# CPU_Board_Connectors.net
KiCad netlist of a schematic drawn in Altium Designer
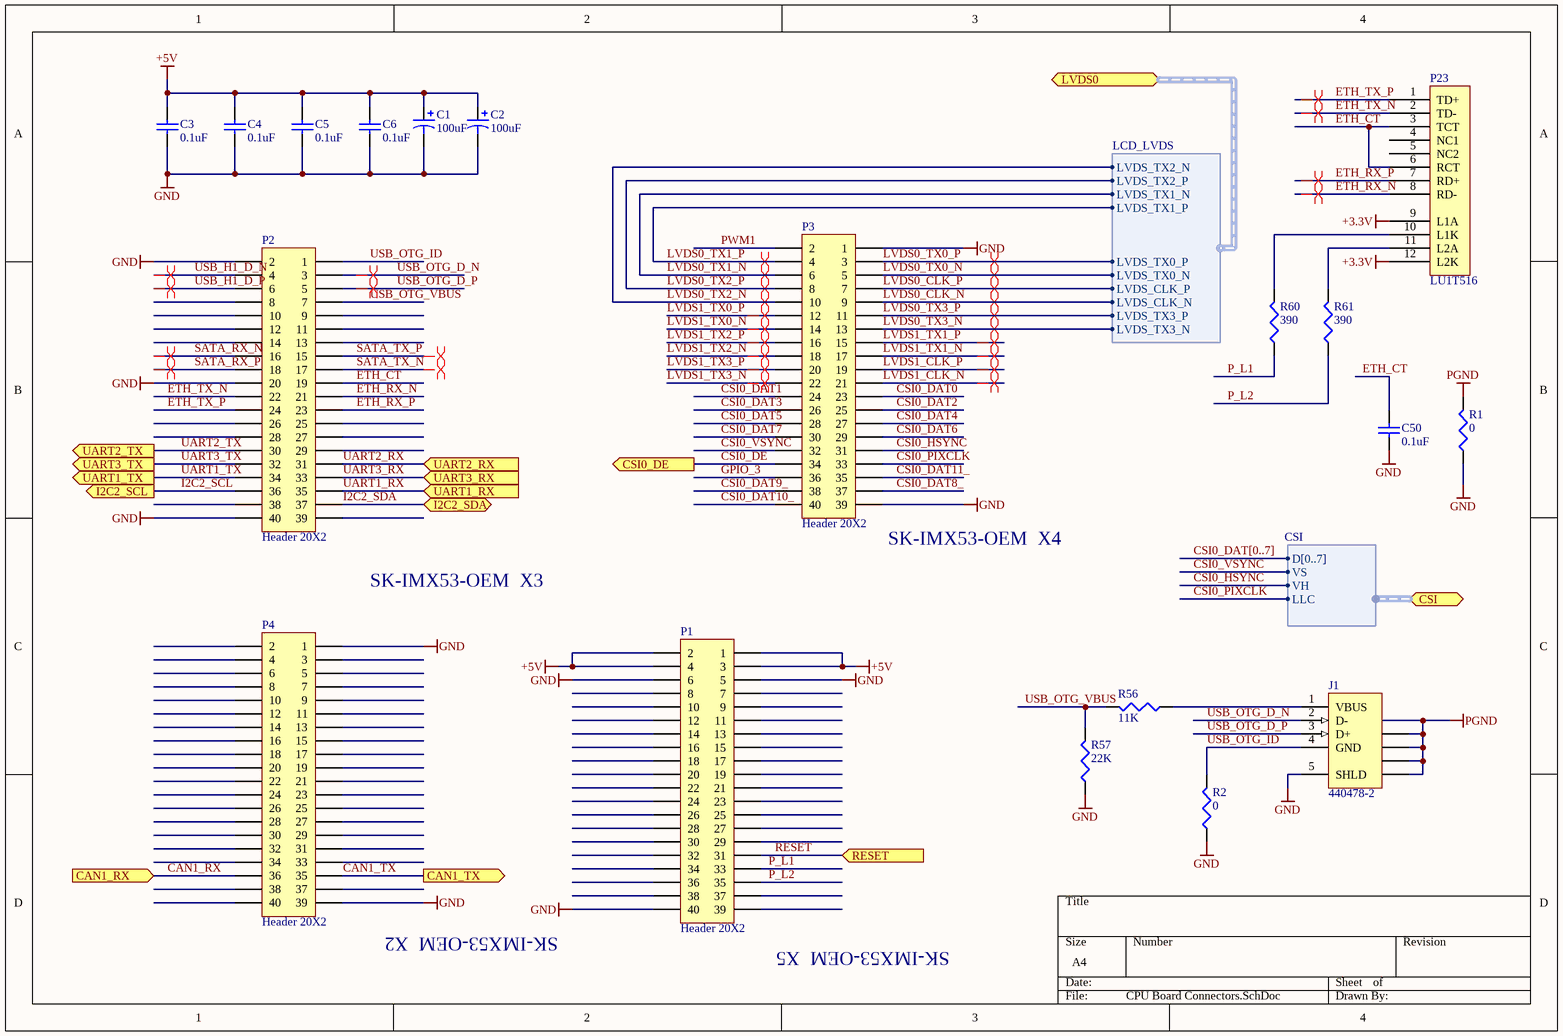
[diagram p0: CPU Board Connectors.SchDoc]

(export (version "E")
  (design (tool "Eeschema 10.0.6"))
  (components
    (comp (ref "C1")
      (value "100uF")
      (footprint "6032")
      (fields (field (name "PUBLISHER") "Altium Limited"))
      (libsource (lib "Vishay Sprague Tantalum Chip Capacitor") (part "893D225X0025C2"))
    )
    (comp (ref "C2")
      (value "100uF")
      (footprint "6032")
      (fields (field (name "PUBLISHER") "Altium Limited"))
      (libsource (lib "Vishay Sprague Tantalum Chip Capacitor") (part "893D225X0025C2"))
    )
    (comp (ref "C3")
      (value "0.1uF")
      (footprint "2012[0805]")
      (description "Ceramic Chip Capacitor - Standard")
      (fields (field (name "PUBLISHER") "Altium Limited"))
      (libsource (lib "ResAndCaps") (part "C0805"))
    )
    (comp (ref "C4")
      (value "0.1uF")
      (footprint "2012[0805]")
      (description "Ceramic Chip Capacitor - Standard")
      (fields (field (name "PUBLISHER") "Altium Limited"))
      (libsource (lib "ResAndCaps") (part "C0805"))
    )
    (comp (ref "C5")
      (value "0.1uF")
      (footprint "2012[0805]")
      (description "Ceramic Chip Capacitor - Standard")
      (fields (field (name "PUBLISHER") "Altium Limited"))
      (libsource (lib "ResAndCaps") (part "C0805"))
    )
    (comp (ref "C6")
      (value "0.1uF")
      (footprint "2012[0805]")
      (description "Ceramic Chip Capacitor - Standard")
      (fields (field (name "PUBLISHER") "Altium Limited"))
      (libsource (lib "ResAndCaps") (part "C0805"))
    )
    (comp (ref "C50")
      (value "0.1uF")
      (footprint "2012[0805]")
      (description "Ceramic Chip Capacitor - Standard")
      (fields (field (name "PUBLISHER") "Altium Limited"))
      (libsource (lib "ResAndCaps") (part "C0805"))
    )
    (comp (ref "J1")
      (value "440478-2")
      (footprint "440478")
      (description "USB 2.0, Right Angle, SMT, A Type, Receptacle, 5 Position, Black")
      (fields (field (name "PUBLISHER") "Altium Limited"))
      (libsource (lib "AMP Serial Bus USB") (part "440478-2"))
    )
    (comp (ref "P1")
      (value "Header 20X2")
      (footprint "HDR2X20_F")
      (description "Header, 20-Pin, Dual row")
      (fields (field (name "PUBLISHER") "Altium Limited"))
      (libsource (lib "Miscellaneous Connectors") (part "Header 20X2"))
    )
    (comp (ref "P2")
      (value "Header 20X2")
      (footprint "HDR2X20_F")
      (description "Header, 20-Pin, Dual row")
      (fields (field (name "PUBLISHER") "Altium Limited"))
      (libsource (lib "Miscellaneous Connectors") (part "Header 20X2"))
    )
    (comp (ref "P3")
      (value "Header 20X2")
      (footprint "HDR2X20_F")
      (description "Header, 20-Pin, Dual row")
      (fields (field (name "PUBLISHER") "Altium Limited"))
      (libsource (lib "Miscellaneous Connectors") (part "Header 20X2"))
    )
    (comp (ref "P4")
      (value "Header 20X2")
      (footprint "HDR2X20_F")
      (description "Header, 20-Pin, Dual row")
      (fields (field (name "PUBLISHER") "Altium Limited"))
      (libsource (lib "Miscellaneous Connectors") (part "Header 20X2"))
    )
    (comp (ref "P23")
      (value "LU1T516")
      (footprint "LU1T516")
      (libsource (lib "ethernet_conns") (part "LU1T516"))
    )
    (comp (ref "R1")
      (value "0")
      (footprint "R2012[0805]")
      (description "R0805")
      (fields (field (name "PUBLISHER") "Altium Limited"))
      (libsource (lib "ResAndCaps") (part "R0805"))
    )
    (comp (ref "R2")
      (value "0")
      (footprint "R2012[0805]")
      (description "R0805")
      (fields (field (name "PUBLISHER") "Altium Limited"))
      (libsource (lib "ResAndCaps") (part "R0805"))
    )
    (comp (ref "R56")
      (value "11K")
      (footprint "R2012[0805]")
      (description "R0805")
      (fields (field (name "PUBLISHER") "Altium Limited"))
      (libsource (lib "ResAndCaps") (part "R0805"))
    )
    (comp (ref "R57")
      (value "22K")
      (footprint "R2012[0805]")
      (description "R0805")
      (fields (field (name "PUBLISHER") "Altium Limited"))
      (libsource (lib "ResAndCaps") (part "R0805"))
    )
    (comp (ref "R60")
      (value "390")
      (footprint "R2012[0805]")
      (description "R0805")
      (fields (field (name "PUBLISHER") "Altium Limited"))
      (libsource (lib "ResAndCaps") (part "R0805"))
    )
    (comp (ref "R61")
      (value "390")
      (footprint "R2012[0805]")
      (description "R0805")
      (fields (field (name "PUBLISHER") "Altium Limited"))
      (libsource (lib "ResAndCaps") (part "R0805"))
    )
  )
  (nets
    (net (code "3") (name "+3.3V") (class "Default")
      (node (ref "P23") (pin "12") (pinfunction "L2K_12") (pintype "passive"))
      (node (ref "P23") (pin "9") (pinfunction "L1A_9") (pintype "passive"))
    )
    (net (code "4") (name "+5V") (class "Default")
      (node (ref "C1") (pin "1") (pinfunction "1_1") (pintype "passive"))
      (node (ref "C2") (pin "1") (pinfunction "1_1") (pintype "passive"))
      (node (ref "C3") (pin "2") (pinfunction "2_2") (pintype "passive"))
      (node (ref "C4") (pin "2") (pinfunction "2_2") (pintype "passive"))
      (node (ref "C5") (pin "2") (pinfunction "2_2") (pintype "passive"))
      (node (ref "C6") (pin "2") (pinfunction "2_2") (pintype "passive"))
      (node (ref "P1") (pin "1") (pinfunction "1_1") (pintype "passive"))
      (node (ref "P1") (pin "2") (pinfunction "2_2") (pintype "passive"))
      (node (ref "P1") (pin "3") (pinfunction "3_3") (pintype "passive"))
      (node (ref "P1") (pin "4") (pinfunction "4_4") (pintype "passive"))
    )
    (net (code "5") (name "/CAN1_RX") (class "Default")
      (node (ref "P4") (pin "36") (pinfunction "36_36") (pintype "passive"))
    )
    (net (code "6") (name "/CAN1_TX") (class "Default")
      (node (ref "P4") (pin "35") (pinfunction "35_35") (pintype "passive"))
    )
    (net (code "7") (name "/CSI0_DAT0") (class "Default")
      (node (ref "P3") (pin "23") (pinfunction "23_23") (pintype "passive"))
    )
    (net (code "8") (name "/CSI0_DAT1") (class "Default")
      (node (ref "P3") (pin "24") (pinfunction "24_24") (pintype "passive"))
    )
    (net (code "9") (name "/CSI0_DAT2") (class "Default")
      (node (ref "P3") (pin "25") (pinfunction "25_25") (pintype "passive"))
    )
    (net (code "10") (name "/CSI0_DAT3") (class "Default")
      (node (ref "P3") (pin "26") (pinfunction "26_26") (pintype "passive"))
    )
    (net (code "11") (name "/CSI0_DAT4") (class "Default")
      (node (ref "P3") (pin "27") (pinfunction "27_27") (pintype "passive"))
    )
    (net (code "12") (name "/CSI0_DAT5") (class "Default")
      (node (ref "P3") (pin "28") (pinfunction "28_28") (pintype "passive"))
    )
    (net (code "13") (name "/CSI0_DAT6") (class "Default")
      (node (ref "P3") (pin "29") (pinfunction "29_29") (pintype "passive"))
    )
    (net (code "14") (name "/CSI0_DAT7") (class "Default")
      (node (ref "P3") (pin "30") (pinfunction "30_30") (pintype "passive"))
    )
    (net (code "15") (name "/CSI0_DAT8_") (class "Default")
      (node (ref "P3") (pin "37") (pinfunction "37_37") (pintype "passive"))
    )
    (net (code "16") (name "/CSI0_DAT9_") (class "Default")
      (node (ref "P3") (pin "38") (pinfunction "38_38") (pintype "passive"))
    )
    (net (code "17") (name "/CSI0_DAT10_") (class "Default")
      (node (ref "P3") (pin "40") (pinfunction "40_40") (pintype "passive"))
    )
    (net (code "18") (name "/CSI0_DAT11_") (class "Default")
      (node (ref "P3") (pin "35") (pinfunction "35_35") (pintype "passive"))
    )
    (net (code "19") (name "/CSI0_DE") (class "Default")
      (node (ref "P3") (pin "34") (pinfunction "34_34") (pintype "passive"))
    )
    (net (code "20") (name "/CSI0_HSYNC") (class "Default")
      (node (ref "P3") (pin "31") (pinfunction "31_31") (pintype "passive"))
    )
    (net (code "21") (name "/CSI0_PIXCLK") (class "Default")
      (node (ref "P3") (pin "33") (pinfunction "33_33") (pintype "passive"))
    )
    (net (code "22") (name "/CSI0_VSYNC") (class "Default")
      (node (ref "P3") (pin "32") (pinfunction "32_32") (pintype "passive"))
    )
    (net (code "24") (name "/ETH_CT") (class "Default")
      (node (ref "C50") (pin "1") (pinfunction "1_1") (pintype "passive"))
      (node (ref "P2") (pin "19") (pinfunction "19_19") (pintype "passive"))
      (node (ref "P23") (pin "3") (pinfunction "TCT_3") (pintype "passive"))
      (node (ref "P23") (pin "6") (pinfunction "RCT_6") (pintype "passive"))
    )
    (net (code "25") (name "/ETH_RX_N") (class "Default")
      (node (ref "P2") (pin "21") (pinfunction "21_21") (pintype "passive"))
      (node (ref "P23") (pin "8") (pinfunction "RD-_8") (pintype "passive"))
    )
    (net (code "26") (name "/ETH_RX_P") (class "Default")
      (node (ref "P2") (pin "23") (pinfunction "23_23") (pintype "passive"))
      (node (ref "P23") (pin "7") (pinfunction "RD+_7") (pintype "passive"))
    )
    (net (code "27") (name "/ETH_TX_N") (class "Default")
      (node (ref "P2") (pin "22") (pinfunction "22_22") (pintype "passive"))
      (node (ref "P23") (pin "2") (pinfunction "TD-_2") (pintype "passive"))
    )
    (net (code "28") (name "/ETH_TX_P") (class "Default")
      (node (ref "P2") (pin "24") (pinfunction "24_24") (pintype "passive"))
      (node (ref "P23") (pin "1") (pinfunction "TD+_1") (pintype "passive"))
    )
    (net (code "29") (name "/GPIO_3") (class "Default")
      (node (ref "P3") (pin "36") (pinfunction "36_36") (pintype "passive"))
    )
    (net (code "30") (name "/I2C2_SCL") (class "Default")
      (node (ref "P2") (pin "36") (pinfunction "36_36") (pintype "passive"))
    )
    (net (code "31") (name "/I2C2_SDA") (class "Default")
      (node (ref "P2") (pin "37") (pinfunction "37_37") (pintype "passive"))
    )
    (net (code "32") (name "/LVDS0_CLK_N") (class "Default")
      (node (ref "P3") (pin "9") (pinfunction "9_9") (pintype "passive"))
    )
    (net (code "33") (name "/LVDS0_CLK_P") (class "Default")
      (node (ref "P3") (pin "7") (pinfunction "7_7") (pintype "passive"))
    )
    (net (code "34") (name "/LVDS0_TX0_N") (class "Default")
      (node (ref "P3") (pin "5") (pinfunction "5_5") (pintype "passive"))
    )
    (net (code "35") (name "/LVDS0_TX0_P") (class "Default")
      (node (ref "P3") (pin "3") (pinfunction "3_3") (pintype "passive"))
    )
    (net (code "36") (name "/LVDS0_TX1_N") (class "Default")
      (node (ref "P3") (pin "6") (pinfunction "6_6") (pintype "passive"))
    )
    (net (code "37") (name "/LVDS0_TX1_P") (class "Default")
      (node (ref "P3") (pin "4") (pinfunction "4_4") (pintype "passive"))
    )
    (net (code "38") (name "/LVDS0_TX2_N") (class "Default")
      (node (ref "P3") (pin "10") (pinfunction "10_10") (pintype "passive"))
    )
    (net (code "39") (name "/LVDS0_TX2_P") (class "Default")
      (node (ref "P3") (pin "8") (pinfunction "8_8") (pintype "passive"))
    )
    (net (code "40") (name "/LVDS0_TX3_N") (class "Default")
      (node (ref "P3") (pin "13") (pinfunction "13_13") (pintype "passive"))
    )
    (net (code "41") (name "/LVDS0_TX3_P") (class "Default")
      (node (ref "P3") (pin "11") (pinfunction "11_11") (pintype "passive"))
    )
    (net (code "42") (name "/LVDS1_CLK_N") (class "Default")
      (node (ref "P3") (pin "21") (pinfunction "21_21") (pintype "passive"))
    )
    (net (code "43") (name "/LVDS1_CLK_P") (class "Default")
      (node (ref "P3") (pin "19") (pinfunction "19_19") (pintype "passive"))
    )
    (net (code "44") (name "/LVDS1_TX0_N") (class "Default")
      (node (ref "P3") (pin "14") (pinfunction "14_14") (pintype "passive"))
    )
    (net (code "45") (name "/LVDS1_TX0_P") (class "Default")
      (node (ref "P3") (pin "12") (pinfunction "12_12") (pintype "passive"))
    )
    (net (code "46") (name "/LVDS1_TX1_N") (class "Default")
      (node (ref "P3") (pin "17") (pinfunction "17_17") (pintype "passive"))
    )
    (net (code "47") (name "/LVDS1_TX1_P") (class "Default")
      (node (ref "P3") (pin "15") (pinfunction "15_15") (pintype "passive"))
    )
    (net (code "48") (name "/LVDS1_TX2_N") (class "Default")
      (node (ref "P3") (pin "18") (pinfunction "18_18") (pintype "passive"))
    )
    (net (code "49") (name "/LVDS1_TX2_P") (class "Default")
      (node (ref "P3") (pin "16") (pinfunction "16_16") (pintype "passive"))
    )
    (net (code "50") (name "/LVDS1_TX3_N") (class "Default")
      (node (ref "P3") (pin "22") (pinfunction "22_22") (pintype "passive"))
    )
    (net (code "51") (name "/LVDS1_TX3_P") (class "Default")
      (node (ref "P3") (pin "20") (pinfunction "20_20") (pintype "passive"))
    )
    (net (code "52") (name "/PWM1") (class "Default")
      (node (ref "P3") (pin "2") (pinfunction "2_2") (pintype "passive"))
    )
    (net (code "53") (name "/P_L1") (class "Default")
      (node (ref "P1") (pin "33") (pinfunction "33_33") (pintype "passive"))
      (node (ref "R60") (pin "1") (pinfunction "1_1") (pintype "passive"))
    )
    (net (code "54") (name "/P_L2") (class "Default")
      (node (ref "P1") (pin "35") (pinfunction "35_35") (pintype "passive"))
      (node (ref "R61") (pin "1") (pinfunction "1_1") (pintype "passive"))
    )
    (net (code "55") (name "/RESET") (class "Default")
      (node (ref "P1") (pin "31") (pinfunction "31_31") (pintype "passive"))
    )
    (net (code "56") (name "/SATA_RX_N") (class "Default")
      (node (ref "P2") (pin "16") (pinfunction "16_16") (pintype "passive"))
    )
    (net (code "57") (name "/SATA_RX_P") (class "Default")
      (node (ref "P2") (pin "18") (pinfunction "18_18") (pintype "passive"))
    )
    (net (code "58") (name "/SATA_TX_N") (class "Default")
      (node (ref "P2") (pin "17") (pinfunction "17_17") (pintype "passive"))
    )
    (net (code "59") (name "/SATA_TX_P") (class "Default")
      (node (ref "P2") (pin "15") (pinfunction "15_15") (pintype "passive"))
    )
    (net (code "60") (name "/UART1_RX") (class "Default")
      (node (ref "P2") (pin "35") (pinfunction "35_35") (pintype "passive"))
    )
    (net (code "61") (name "/UART1_TX") (class "Default")
      (node (ref "P2") (pin "34") (pinfunction "34_34") (pintype "passive"))
    )
    (net (code "62") (name "/UART2_RX") (class "Default")
      (node (ref "P2") (pin "31") (pinfunction "31_31") (pintype "passive"))
    )
    (net (code "63") (name "/UART2_TX") (class "Default")
      (node (ref "P2") (pin "30") (pinfunction "30_30") (pintype "passive"))
    )
    (net (code "64") (name "/UART3_RX") (class "Default")
      (node (ref "P2") (pin "33") (pinfunction "33_33") (pintype "passive"))
    )
    (net (code "65") (name "/UART3_TX") (class "Default")
      (node (ref "P2") (pin "32") (pinfunction "32_32") (pintype "passive"))
    )
    (net (code "66") (name "/USB_H1_D_N") (class "Default")
      (node (ref "P2") (pin "4") (pinfunction "4_4") (pintype "passive"))
    )
    (net (code "67") (name "/USB_H1_D_P") (class "Default")
      (node (ref "P2") (pin "6") (pinfunction "6_6") (pintype "passive"))
    )
    (net (code "68") (name "/USB_OTG_D_N") (class "Default")
      (node (ref "J1") (pin "2") (pinfunction "D-_2") (pintype "input"))
      (node (ref "P2") (pin "3") (pinfunction "3_3") (pintype "passive"))
    )
    (net (code "69") (name "/USB_OTG_D_P") (class "Default")
      (node (ref "J1") (pin "3") (pinfunction "D+_3") (pintype "input"))
      (node (ref "P2") (pin "5") (pinfunction "5_5") (pintype "passive"))
    )
    (net (code "70") (name "/USB_OTG_ID") (class "Default")
      (node (ref "J1") (pin "4") (pinfunction "GND_4") (pintype "power_in"))
      (node (ref "P2") (pin "1") (pinfunction "1_1") (pintype "passive"))
      (node (ref "R2") (pin "2") (pinfunction "2_2") (pintype "passive"))
    )
    (net (code "71") (name "/USB_OTG_VBUS") (class "Default")
      (node (ref "P2") (pin "7") (pinfunction "7_7") (pintype "passive"))
      (node (ref "R56") (pin "2") (pinfunction "2_2") (pintype "passive"))
      (node (ref "R57") (pin "2") (pinfunction "2_2") (pintype "passive"))
    )
    (net (code "74") (name "GND") (class "Default")
      (node (ref "C1") (pin "2") (pinfunction "2_2") (pintype "passive"))
      (node (ref "C2") (pin "2") (pinfunction "2_2") (pintype "passive"))
      (node (ref "C3") (pin "1") (pinfunction "1_1") (pintype "passive"))
      (node (ref "C4") (pin "1") (pinfunction "1_1") (pintype "passive"))
      (node (ref "C5") (pin "1") (pinfunction "1_1") (pintype "passive"))
      (node (ref "C50") (pin "2") (pinfunction "2_2") (pintype "passive"))
      (node (ref "C6") (pin "1") (pinfunction "1_1") (pintype "passive"))
      (node (ref "J1") (pin "5") (pinfunction "SHLD_5") (pintype "passive"))
      (node (ref "P1") (pin "40") (pinfunction "40_40") (pintype "passive"))
      (node (ref "P1") (pin "5") (pinfunction "5_5") (pintype "passive"))
      (node (ref "P1") (pin "6") (pinfunction "6_6") (pintype "passive"))
      (node (ref "P2") (pin "2") (pinfunction "2_2") (pintype "passive"))
      (node (ref "P2") (pin "20") (pinfunction "20_20") (pintype "passive"))
      (node (ref "P2") (pin "40") (pinfunction "40_40") (pintype "passive"))
      (node (ref "P3") (pin "1") (pinfunction "1_1") (pintype "passive"))
      (node (ref "P3") (pin "39") (pinfunction "39_39") (pintype "passive"))
      (node (ref "P4") (pin "1") (pinfunction "1_1") (pintype "passive"))
      (node (ref "P4") (pin "39") (pinfunction "39_39") (pintype "passive"))
      (node (ref "R1") (pin "1") (pinfunction "1_1") (pintype "passive"))
      (node (ref "R2") (pin "1") (pinfunction "1_1") (pintype "passive"))
      (node (ref "R57") (pin "1") (pinfunction "1_1") (pintype "passive"))
    )
    (net (code "75") (name "Net-(J1-VBUS)") (class "Default")
      (node (ref "J1") (pin "1") (pinfunction "VBUS_1") (pintype "power_in"))
      (node (ref "R56") (pin "1") (pinfunction "1_1") (pintype "passive"))
    )
    (net (code "76") (name "Net-(P23-L1K)") (class "Default")
      (node (ref "P23") (pin "10") (pinfunction "L1K_10") (pintype "passive"))
      (node (ref "R60") (pin "2") (pinfunction "2_2") (pintype "passive"))
    )
    (net (code "77") (name "Net-(P23-L2A)") (class "Default")
      (node (ref "P23") (pin "11") (pinfunction "L2A_11") (pintype "passive"))
      (node (ref "R61") (pin "2") (pinfunction "2_2") (pintype "passive"))
    )
    (net (code "78") (name "PGND") (class "Default")
      (node (ref "J1") (pin "6") (pinfunction "SHLD_6") (pintype "passive"))
      (node (ref "J1") (pin "7") (pinfunction "SHLD_7") (pintype "passive"))
      (node (ref "J1") (pin "8") (pinfunction "SHLD_8") (pintype "passive"))
      (node (ref "J1") (pin "9") (pinfunction "SHLD_9") (pintype "passive"))
      (node (ref "R1") (pin "2") (pinfunction "2_2") (pintype "passive"))
    )
    (net (code "79") (name "unconnected-(P1-Pad7)") (class "Default")
      (node (ref "P1") (pin "7") (pinfunction "7_7") (pintype "passive"))
    )
    (net (code "80") (name "unconnected-(P1-Pad8)") (class "Default")
      (node (ref "P1") (pin "8") (pinfunction "8_8") (pintype "passive"))
    )
    (net (code "81") (name "unconnected-(P1-Pad9)") (class "Default")
      (node (ref "P1") (pin "9") (pinfunction "9_9") (pintype "passive"))
    )
    (net (code "82") (name "unconnected-(P1-Pad10)") (class "Default")
      (node (ref "P1") (pin "10") (pinfunction "10_10") (pintype "passive"))
    )
    (net (code "83") (name "unconnected-(P1-Pad11)") (class "Default")
      (node (ref "P1") (pin "11") (pinfunction "11_11") (pintype "passive"))
    )
    (net (code "84") (name "unconnected-(P1-Pad12)") (class "Default")
      (node (ref "P1") (pin "12") (pinfunction "12_12") (pintype "passive"))
    )
    (net (code "85") (name "unconnected-(P1-Pad13)") (class "Default")
      (node (ref "P1") (pin "13") (pinfunction "13_13") (pintype "passive"))
    )
    (net (code "86") (name "unconnected-(P1-Pad14)") (class "Default")
      (node (ref "P1") (pin "14") (pinfunction "14_14") (pintype "passive"))
    )
    (net (code "87") (name "unconnected-(P1-Pad15)") (class "Default")
      (node (ref "P1") (pin "15") (pinfunction "15_15") (pintype "passive"))
    )
    (net (code "88") (name "unconnected-(P1-Pad16)") (class "Default")
      (node (ref "P1") (pin "16") (pinfunction "16_16") (pintype "passive"))
    )
    (net (code "89") (name "unconnected-(P1-Pad17)") (class "Default")
      (node (ref "P1") (pin "17") (pinfunction "17_17") (pintype "passive"))
    )
    (net (code "90") (name "unconnected-(P1-Pad18)") (class "Default")
      (node (ref "P1") (pin "18") (pinfunction "18_18") (pintype "passive"))
    )
    (net (code "91") (name "unconnected-(P1-Pad19)") (class "Default")
      (node (ref "P1") (pin "19") (pinfunction "19_19") (pintype "passive"))
    )
    (net (code "92") (name "unconnected-(P1-Pad20)") (class "Default")
      (node (ref "P1") (pin "20") (pinfunction "20_20") (pintype "passive"))
    )
    (net (code "93") (name "unconnected-(P1-Pad21)") (class "Default")
      (node (ref "P1") (pin "21") (pinfunction "21_21") (pintype "passive"))
    )
    (net (code "94") (name "unconnected-(P1-Pad22)") (class "Default")
      (node (ref "P1") (pin "22") (pinfunction "22_22") (pintype "passive"))
    )
    (net (code "95") (name "unconnected-(P1-Pad23)") (class "Default")
      (node (ref "P1") (pin "23") (pinfunction "23_23") (pintype "passive"))
    )
    (net (code "96") (name "unconnected-(P1-Pad24)") (class "Default")
      (node (ref "P1") (pin "24") (pinfunction "24_24") (pintype "passive"))
    )
    (net (code "97") (name "unconnected-(P1-Pad25)") (class "Default")
      (node (ref "P1") (pin "25") (pinfunction "25_25") (pintype "passive"))
    )
    (net (code "98") (name "unconnected-(P1-Pad26)") (class "Default")
      (node (ref "P1") (pin "26") (pinfunction "26_26") (pintype "passive"))
    )
    (net (code "99") (name "unconnected-(P1-Pad27)") (class "Default")
      (node (ref "P1") (pin "27") (pinfunction "27_27") (pintype "passive"))
    )
    (net (code "100") (name "unconnected-(P1-Pad28)") (class "Default")
      (node (ref "P1") (pin "28") (pinfunction "28_28") (pintype "passive"))
    )
    (net (code "101") (name "unconnected-(P1-Pad29)") (class "Default")
      (node (ref "P1") (pin "29") (pinfunction "29_29") (pintype "passive"))
    )
    (net (code "102") (name "unconnected-(P1-Pad30)") (class "Default")
      (node (ref "P1") (pin "30") (pinfunction "30_30") (pintype "passive"))
    )
    (net (code "103") (name "unconnected-(P1-Pad32)") (class "Default")
      (node (ref "P1") (pin "32") (pinfunction "32_32") (pintype "passive"))
    )
    (net (code "104") (name "unconnected-(P1-Pad34)") (class "Default")
      (node (ref "P1") (pin "34") (pinfunction "34_34") (pintype "passive"))
    )
    (net (code "105") (name "unconnected-(P1-Pad36)") (class "Default")
      (node (ref "P1") (pin "36") (pinfunction "36_36") (pintype "passive"))
    )
    (net (code "106") (name "unconnected-(P1-Pad37)") (class "Default")
      (node (ref "P1") (pin "37") (pinfunction "37_37") (pintype "passive"))
    )
    (net (code "107") (name "unconnected-(P1-Pad38)") (class "Default")
      (node (ref "P1") (pin "38") (pinfunction "38_38") (pintype "passive"))
    )
    (net (code "108") (name "unconnected-(P1-Pad39)") (class "Default")
      (node (ref "P1") (pin "39") (pinfunction "39_39") (pintype "passive"))
    )
    (net (code "109") (name "unconnected-(P2-Pad8)") (class "Default")
      (node (ref "P2") (pin "8") (pinfunction "8_8") (pintype "passive"))
    )
    (net (code "110") (name "unconnected-(P2-Pad9)") (class "Default")
      (node (ref "P2") (pin "9") (pinfunction "9_9") (pintype "passive"))
    )
    (net (code "111") (name "unconnected-(P2-Pad10)") (class "Default")
      (node (ref "P2") (pin "10") (pinfunction "10_10") (pintype "passive"))
    )
    (net (code "112") (name "unconnected-(P2-Pad11)") (class "Default")
      (node (ref "P2") (pin "11") (pinfunction "11_11") (pintype "passive"))
    )
    (net (code "113") (name "unconnected-(P2-Pad12)") (class "Default")
      (node (ref "P2") (pin "12") (pinfunction "12_12") (pintype "passive"))
    )
    (net (code "114") (name "unconnected-(P2-Pad13)") (class "Default")
      (node (ref "P2") (pin "13") (pinfunction "13_13") (pintype "passive"))
    )
    (net (code "115") (name "unconnected-(P2-Pad14)") (class "Default")
      (node (ref "P2") (pin "14") (pinfunction "14_14") (pintype "passive"))
    )
    (net (code "116") (name "unconnected-(P2-Pad25)") (class "Default")
      (node (ref "P2") (pin "25") (pinfunction "25_25") (pintype "passive"))
    )
    (net (code "117") (name "unconnected-(P2-Pad26)") (class "Default")
      (node (ref "P2") (pin "26") (pinfunction "26_26") (pintype "passive"))
    )
    (net (code "118") (name "unconnected-(P2-Pad27)") (class "Default")
      (node (ref "P2") (pin "27") (pinfunction "27_27") (pintype "passive"))
    )
    (net (code "119") (name "unconnected-(P2-Pad28)") (class "Default")
      (node (ref "P2") (pin "28") (pinfunction "28_28") (pintype "passive"))
    )
    (net (code "120") (name "unconnected-(P2-Pad29)") (class "Default")
      (node (ref "P2") (pin "29") (pinfunction "29_29") (pintype "passive"))
    )
    (net (code "121") (name "unconnected-(P2-Pad38)") (class "Default")
      (node (ref "P2") (pin "38") (pinfunction "38_38") (pintype "passive"))
    )
    (net (code "122") (name "unconnected-(P2-Pad39)") (class "Default")
      (node (ref "P2") (pin "39") (pinfunction "39_39") (pintype "passive"))
    )
    (net (code "123") (name "unconnected-(P4-Pad2)") (class "Default")
      (node (ref "P4") (pin "2") (pinfunction "2_2") (pintype "passive"))
    )
    (net (code "124") (name "unconnected-(P4-Pad3)") (class "Default")
      (node (ref "P4") (pin "3") (pinfunction "3_3") (pintype "passive"))
    )
    (net (code "125") (name "unconnected-(P4-Pad4)") (class "Default")
      (node (ref "P4") (pin "4") (pinfunction "4_4") (pintype "passive"))
    )
    (net (code "126") (name "unconnected-(P4-Pad5)") (class "Default")
      (node (ref "P4") (pin "5") (pinfunction "5_5") (pintype "passive"))
    )
    (net (code "127") (name "unconnected-(P4-Pad6)") (class "Default")
      (node (ref "P4") (pin "6") (pinfunction "6_6") (pintype "passive"))
    )
    (net (code "128") (name "unconnected-(P4-Pad7)") (class "Default")
      (node (ref "P4") (pin "7") (pinfunction "7_7") (pintype "passive"))
    )
    (net (code "129") (name "unconnected-(P4-Pad8)") (class "Default")
      (node (ref "P4") (pin "8") (pinfunction "8_8") (pintype "passive"))
    )
    (net (code "130") (name "unconnected-(P4-Pad9)") (class "Default")
      (node (ref "P4") (pin "9") (pinfunction "9_9") (pintype "passive"))
    )
    (net (code "131") (name "unconnected-(P4-Pad10)") (class "Default")
      (node (ref "P4") (pin "10") (pinfunction "10_10") (pintype "passive"))
    )
    (net (code "132") (name "unconnected-(P4-Pad11)") (class "Default")
      (node (ref "P4") (pin "11") (pinfunction "11_11") (pintype "passive"))
    )
    (net (code "133") (name "unconnected-(P4-Pad12)") (class "Default")
      (node (ref "P4") (pin "12") (pinfunction "12_12") (pintype "passive"))
    )
    (net (code "134") (name "unconnected-(P4-Pad13)") (class "Default")
      (node (ref "P4") (pin "13") (pinfunction "13_13") (pintype "passive"))
    )
    (net (code "135") (name "unconnected-(P4-Pad14)") (class "Default")
      (node (ref "P4") (pin "14") (pinfunction "14_14") (pintype "passive"))
    )
    (net (code "136") (name "unconnected-(P4-Pad15)") (class "Default")
      (node (ref "P4") (pin "15") (pinfunction "15_15") (pintype "passive"))
    )
    (net (code "137") (name "unconnected-(P4-Pad16)") (class "Default")
      (node (ref "P4") (pin "16") (pinfunction "16_16") (pintype "passive"))
    )
    (net (code "138") (name "unconnected-(P4-Pad17)") (class "Default")
      (node (ref "P4") (pin "17") (pinfunction "17_17") (pintype "passive"))
    )
    (net (code "139") (name "unconnected-(P4-Pad18)") (class "Default")
      (node (ref "P4") (pin "18") (pinfunction "18_18") (pintype "passive"))
    )
    (net (code "140") (name "unconnected-(P4-Pad19)") (class "Default")
      (node (ref "P4") (pin "19") (pinfunction "19_19") (pintype "passive"))
    )
    (net (code "141") (name "unconnected-(P4-Pad20)") (class "Default")
      (node (ref "P4") (pin "20") (pinfunction "20_20") (pintype "passive"))
    )
    (net (code "142") (name "unconnected-(P4-Pad21)") (class "Default")
      (node (ref "P4") (pin "21") (pinfunction "21_21") (pintype "passive"))
    )
    (net (code "143") (name "unconnected-(P4-Pad22)") (class "Default")
      (node (ref "P4") (pin "22") (pinfunction "22_22") (pintype "passive"))
    )
    (net (code "144") (name "unconnected-(P4-Pad23)") (class "Default")
      (node (ref "P4") (pin "23") (pinfunction "23_23") (pintype "passive"))
    )
    (net (code "145") (name "unconnected-(P4-Pad24)") (class "Default")
      (node (ref "P4") (pin "24") (pinfunction "24_24") (pintype "passive"))
    )
    (net (code "146") (name "unconnected-(P4-Pad25)") (class "Default")
      (node (ref "P4") (pin "25") (pinfunction "25_25") (pintype "passive"))
    )
    (net (code "147") (name "unconnected-(P4-Pad26)") (class "Default")
      (node (ref "P4") (pin "26") (pinfunction "26_26") (pintype "passive"))
    )
    (net (code "148") (name "unconnected-(P4-Pad27)") (class "Default")
      (node (ref "P4") (pin "27") (pinfunction "27_27") (pintype "passive"))
    )
    (net (code "149") (name "unconnected-(P4-Pad28)") (class "Default")
      (node (ref "P4") (pin "28") (pinfunction "28_28") (pintype "passive"))
    )
    (net (code "150") (name "unconnected-(P4-Pad29)") (class "Default")
      (node (ref "P4") (pin "29") (pinfunction "29_29") (pintype "passive"))
    )
    (net (code "151") (name "unconnected-(P4-Pad30)") (class "Default")
      (node (ref "P4") (pin "30") (pinfunction "30_30") (pintype "passive"))
    )
    (net (code "152") (name "unconnected-(P4-Pad31)") (class "Default")
      (node (ref "P4") (pin "31") (pinfunction "31_31") (pintype "passive"))
    )
    (net (code "153") (name "unconnected-(P4-Pad32)") (class "Default")
      (node (ref "P4") (pin "32") (pinfunction "32_32") (pintype "passive"))
    )
    (net (code "154") (name "unconnected-(P4-Pad33)") (class "Default")
      (node (ref "P4") (pin "33") (pinfunction "33_33") (pintype "passive"))
    )
    (net (code "155") (name "unconnected-(P4-Pad34)") (class "Default")
      (node (ref "P4") (pin "34") (pinfunction "34_34") (pintype "passive"))
    )
    (net (code "156") (name "unconnected-(P4-Pad37)") (class "Default")
      (node (ref "P4") (pin "37") (pinfunction "37_37") (pintype "passive"))
    )
    (net (code "157") (name "unconnected-(P4-Pad38)") (class "Default")
      (node (ref "P4") (pin "38") (pinfunction "38_38") (pintype "passive"))
    )
    (net (code "158") (name "unconnected-(P4-Pad40)") (class "Default")
      (node (ref "P4") (pin "40") (pinfunction "40_40") (pintype "passive"))
    )
    (net (code "159") (name "unconnected-(P23-NC1-Pad4)") (class "Default")
      (node (ref "P23") (pin "4") (pinfunction "NC1_4") (pintype "passive"))
    )
    (net (code "160") (name "unconnected-(P23-NC2-Pad5)") (class "Default")
      (node (ref "P23") (pin "5") (pinfunction "NC2_5") (pintype "passive"))
    )
  )
)
